# etb_driver.net
KiCad netlist of a schematic drawn in Altium Designer
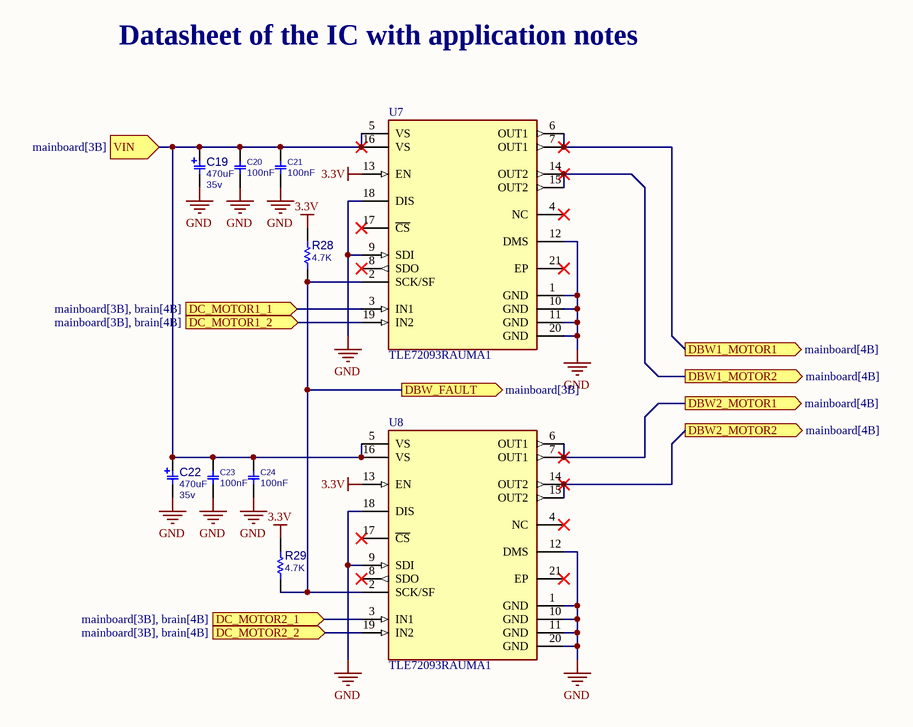
[diagram p0: etb_driver.SchDoc]

(export (version "E")
  (design (tool "Eeschema 10.0.6"))
  (components
    (comp (ref "C19")
      (value "470uF")
      (footprint "C_EL_D10L10")
      (description "CAP, SMD, ELEC,")
      (fields
        (field (name "MANF_P#") "MANF_PART#")
        (field (name "MANF") "MANF")
        (field (name "PARAM2") "35v")
      )
      (libsource (lib "passive_smd") (part "CAP_SMD_EL_470uF_35v"))
    )
    (comp (ref "C20")
      (value "100nF")
      (footprint "C1206")
      (description "CAP, MLCC")
      (fields (field (name "MANF_P#") "MANF_PART#"))
      (libsource (lib "passive_smd") (part "CAP_SMD_MLCC_1206"))
    )
    (comp (ref "C21")
      (value "100nF")
      (footprint "C1206")
      (description "CAP, MLCC")
      (fields (field (name "MANF_P#") "MANF_PART#"))
      (libsource (lib "passive_smd") (part "CAP_SMD_MLCC_1206"))
    )
    (comp (ref "C22")
      (value "470uF")
      (footprint "C_EL_D10L10")
      (description "CAP, SMD, ELEC,")
      (fields
        (field (name "MANF_P#") "MANF_PART#")
        (field (name "MANF") "MANF")
        (field (name "PARAM2") "35v")
      )
      (libsource (lib "passive_smd") (part "CAP_SMD_EL_470uF_35v"))
    )
    (comp (ref "C23")
      (value "100nF")
      (footprint "C1206")
      (description "CAP, MLCC")
      (fields (field (name "MANF_P#") "MANF_PART#"))
      (libsource (lib "passive_smd") (part "CAP_SMD_MLCC_1206"))
    )
    (comp (ref "C24")
      (value "100nF")
      (footprint "C1206")
      (description "CAP, MLCC")
      (fields (field (name "MANF_P#") "MANF_PART#"))
      (libsource (lib "passive_smd") (part "CAP_SMD_MLCC_1206"))
    )
    (comp (ref "R28")
      (value "4.7K")
      (footprint "R0805")
      (description "RESISTOR, SMD")
      (libsource (lib "passive_smd") (part "RES_SMD_0805"))
    )
    (comp (ref "R29")
      (value "4.7K")
      (footprint "R0805")
      (description "RESISTOR, SMD")
      (libsource (lib "passive_smd") (part "RES_SMD_0805"))
    )
    (comp (ref "U7")
      (value "TLE72093RAUMA1")
      (footprint "FP-PG-DSO-20-MFG")
      (description "IC MOTOR DRIVER 3.5V-5.5V 20DSO")
      (libsource (lib "Alib") (part "TLE7209"))
    )
    (comp (ref "U8")
      (value "TLE72093RAUMA1")
      (footprint "FP-PG-DSO-20-MFG")
      (description "IC MOTOR DRIVER 3.5V-5.5V 20DSO")
      (libsource (lib "Alib") (part "TLE7209"))
    )
  )
  (nets
    (net (code "1") (name "/DBW1_MOTOR1") (class "Default")
      (node (ref "U7") (pin "6") (pinfunction "OUT1_6") (pintype "output"))
      (node (ref "U7") (pin "7") (pinfunction "OUT1_7") (pintype "output"))
    )
    (net (code "2") (name "/DBW1_MOTOR2") (class "Default")
      (node (ref "U7") (pin "14") (pinfunction "OUT2_14") (pintype "output"))
      (node (ref "U7") (pin "15") (pinfunction "OUT2_15") (pintype "output"))
    )
    (net (code "3") (name "/DBW2_MOTOR1") (class "Default")
      (node (ref "U8") (pin "6") (pinfunction "OUT1_6") (pintype "output"))
      (node (ref "U8") (pin "7") (pinfunction "OUT1_7") (pintype "output"))
    )
    (net (code "4") (name "/DBW2_MOTOR2") (class "Default")
      (node (ref "U8") (pin "14") (pinfunction "OUT2_14") (pintype "output"))
      (node (ref "U8") (pin "15") (pinfunction "OUT2_15") (pintype "output"))
    )
    (net (code "5") (name "/DBW_FAULT") (class "Default")
      (node (ref "R28") (pin "1") (pinfunction "1_1") (pintype "passive"))
      (node (ref "R29") (pin "1") (pinfunction "1_1") (pintype "passive"))
      (node (ref "U7") (pin "2") (pinfunction "SCK/SF_2") (pintype "passive"))
      (node (ref "U8") (pin "2") (pinfunction "SCK/SF_2") (pintype "passive"))
    )
    (net (code "6") (name "/DC_MOTOR1_1") (class "Default")
      (node (ref "U7") (pin "3") (pinfunction "IN1_3") (pintype "input"))
    )
    (net (code "7") (name "/DC_MOTOR1_2") (class "Default")
      (node (ref "U7") (pin "19") (pinfunction "IN2_19") (pintype "input"))
    )
    (net (code "8") (name "/DC_MOTOR2_1") (class "Default")
      (node (ref "U8") (pin "3") (pinfunction "IN1_3") (pintype "input"))
    )
    (net (code "9") (name "/DC_MOTOR2_2") (class "Default")
      (node (ref "U8") (pin "19") (pinfunction "IN2_19") (pintype "input"))
    )
    (net (code "10") (name "/VIN") (class "Default")
      (node (ref "C19") (pin "1") (pinfunction "1_1") (pintype "passive"))
      (node (ref "C20") (pin "2") (pinfunction "2_2") (pintype "passive"))
      (node (ref "C21") (pin "2") (pinfunction "2_2") (pintype "passive"))
      (node (ref "C22") (pin "1") (pinfunction "1_1") (pintype "passive"))
      (node (ref "C23") (pin "2") (pinfunction "2_2") (pintype "passive"))
      (node (ref "C24") (pin "2") (pinfunction "2_2") (pintype "passive"))
      (node (ref "U7") (pin "16") (pinfunction "VS_16") (pintype "power_in"))
      (node (ref "U7") (pin "5") (pinfunction "VS_5") (pintype "power_in"))
      (node (ref "U8") (pin "16") (pinfunction "VS_16") (pintype "power_in"))
      (node (ref "U8") (pin "5") (pinfunction "VS_5") (pintype "power_in"))
    )
    (net (code "11") (name "3.3V") (class "Default")
      (node (ref "R28") (pin "2") (pinfunction "2_2") (pintype "passive"))
      (node (ref "R29") (pin "2") (pinfunction "2_2") (pintype "passive"))
      (node (ref "U7") (pin "13") (pinfunction "EN_13") (pintype "input"))
      (node (ref "U8") (pin "13") (pinfunction "EN_13") (pintype "input"))
    )
    (net (code "12") (name "GND") (class "Default")
      (node (ref "C19") (pin "2") (pinfunction "2_2") (pintype "passive"))
      (node (ref "C20") (pin "1") (pinfunction "1_1") (pintype "passive"))
      (node (ref "C21") (pin "1") (pinfunction "1_1") (pintype "passive"))
      (node (ref "C22") (pin "2") (pinfunction "2_2") (pintype "passive"))
      (node (ref "C23") (pin "1") (pinfunction "1_1") (pintype "passive"))
      (node (ref "C24") (pin "1") (pinfunction "1_1") (pintype "passive"))
      (node (ref "U7") (pin "1") (pinfunction "GND_1") (pintype "power_in"))
      (node (ref "U7") (pin "10") (pinfunction "GND_10") (pintype "power_in"))
      (node (ref "U7") (pin "11") (pinfunction "GND_11") (pintype "power_in"))
      (node (ref "U7") (pin "12") (pinfunction "DMS_12") (pintype "passive"))
      (node (ref "U7") (pin "18") (pinfunction "DIS_18") (pintype "passive"))
      (node (ref "U7") (pin "20") (pinfunction "GND_20") (pintype "power_in"))
      (node (ref "U7") (pin "9") (pinfunction "SDI_9") (pintype "input"))
      (node (ref "U8") (pin "1") (pinfunction "GND_1") (pintype "power_in"))
      (node (ref "U8") (pin "10") (pinfunction "GND_10") (pintype "power_in"))
      (node (ref "U8") (pin "11") (pinfunction "GND_11") (pintype "power_in"))
      (node (ref "U8") (pin "12") (pinfunction "DMS_12") (pintype "passive"))
      (node (ref "U8") (pin "18") (pinfunction "DIS_18") (pintype "passive"))
      (node (ref "U8") (pin "20") (pinfunction "GND_20") (pintype "power_in"))
      (node (ref "U8") (pin "9") (pinfunction "SDI_9") (pintype "input"))
    )
    (net (code "13") (name "unconnected-(U7-EP-Pad21)") (class "Default")
      (node (ref "U7") (pin "21") (pinfunction "EP_21") (pintype "power_in+no_connect"))
    )
    (net (code "14") (name "unconnected-(U7-NC-Pad4)") (class "Default")
      (node (ref "U7") (pin "4") (pinfunction "NC_4") (pintype "passive+no_connect"))
    )
    (net (code "15") (name "unconnected-(U7-SDO-Pad8)") (class "Default")
      (node (ref "U7") (pin "8") (pinfunction "SDO_8") (pintype "output+no_connect"))
    )
    (net (code "16") (name "unconnected-(U7-~{CS}-Pad17)") (class "Default")
      (node (ref "U7") (pin "17") (pinfunction "~{CS}_17") (pintype "passive+no_connect"))
    )
    (net (code "17") (name "unconnected-(U8-EP-Pad21)") (class "Default")
      (node (ref "U8") (pin "21") (pinfunction "EP_21") (pintype "power_in+no_connect"))
    )
    (net (code "18") (name "unconnected-(U8-NC-Pad4)") (class "Default")
      (node (ref "U8") (pin "4") (pinfunction "NC_4") (pintype "passive+no_connect"))
    )
    (net (code "19") (name "unconnected-(U8-SDO-Pad8)") (class "Default")
      (node (ref "U8") (pin "8") (pinfunction "SDO_8") (pintype "output+no_connect"))
    )
    (net (code "20") (name "unconnected-(U8-~{CS}-Pad17)") (class "Default")
      (node (ref "U8") (pin "17") (pinfunction "~{CS}_17") (pintype "passive+no_connect"))
    )
  )
)
